# ESP32V1_based_led_button.net
KiCad netlist of a schematic drawn in EAGLE
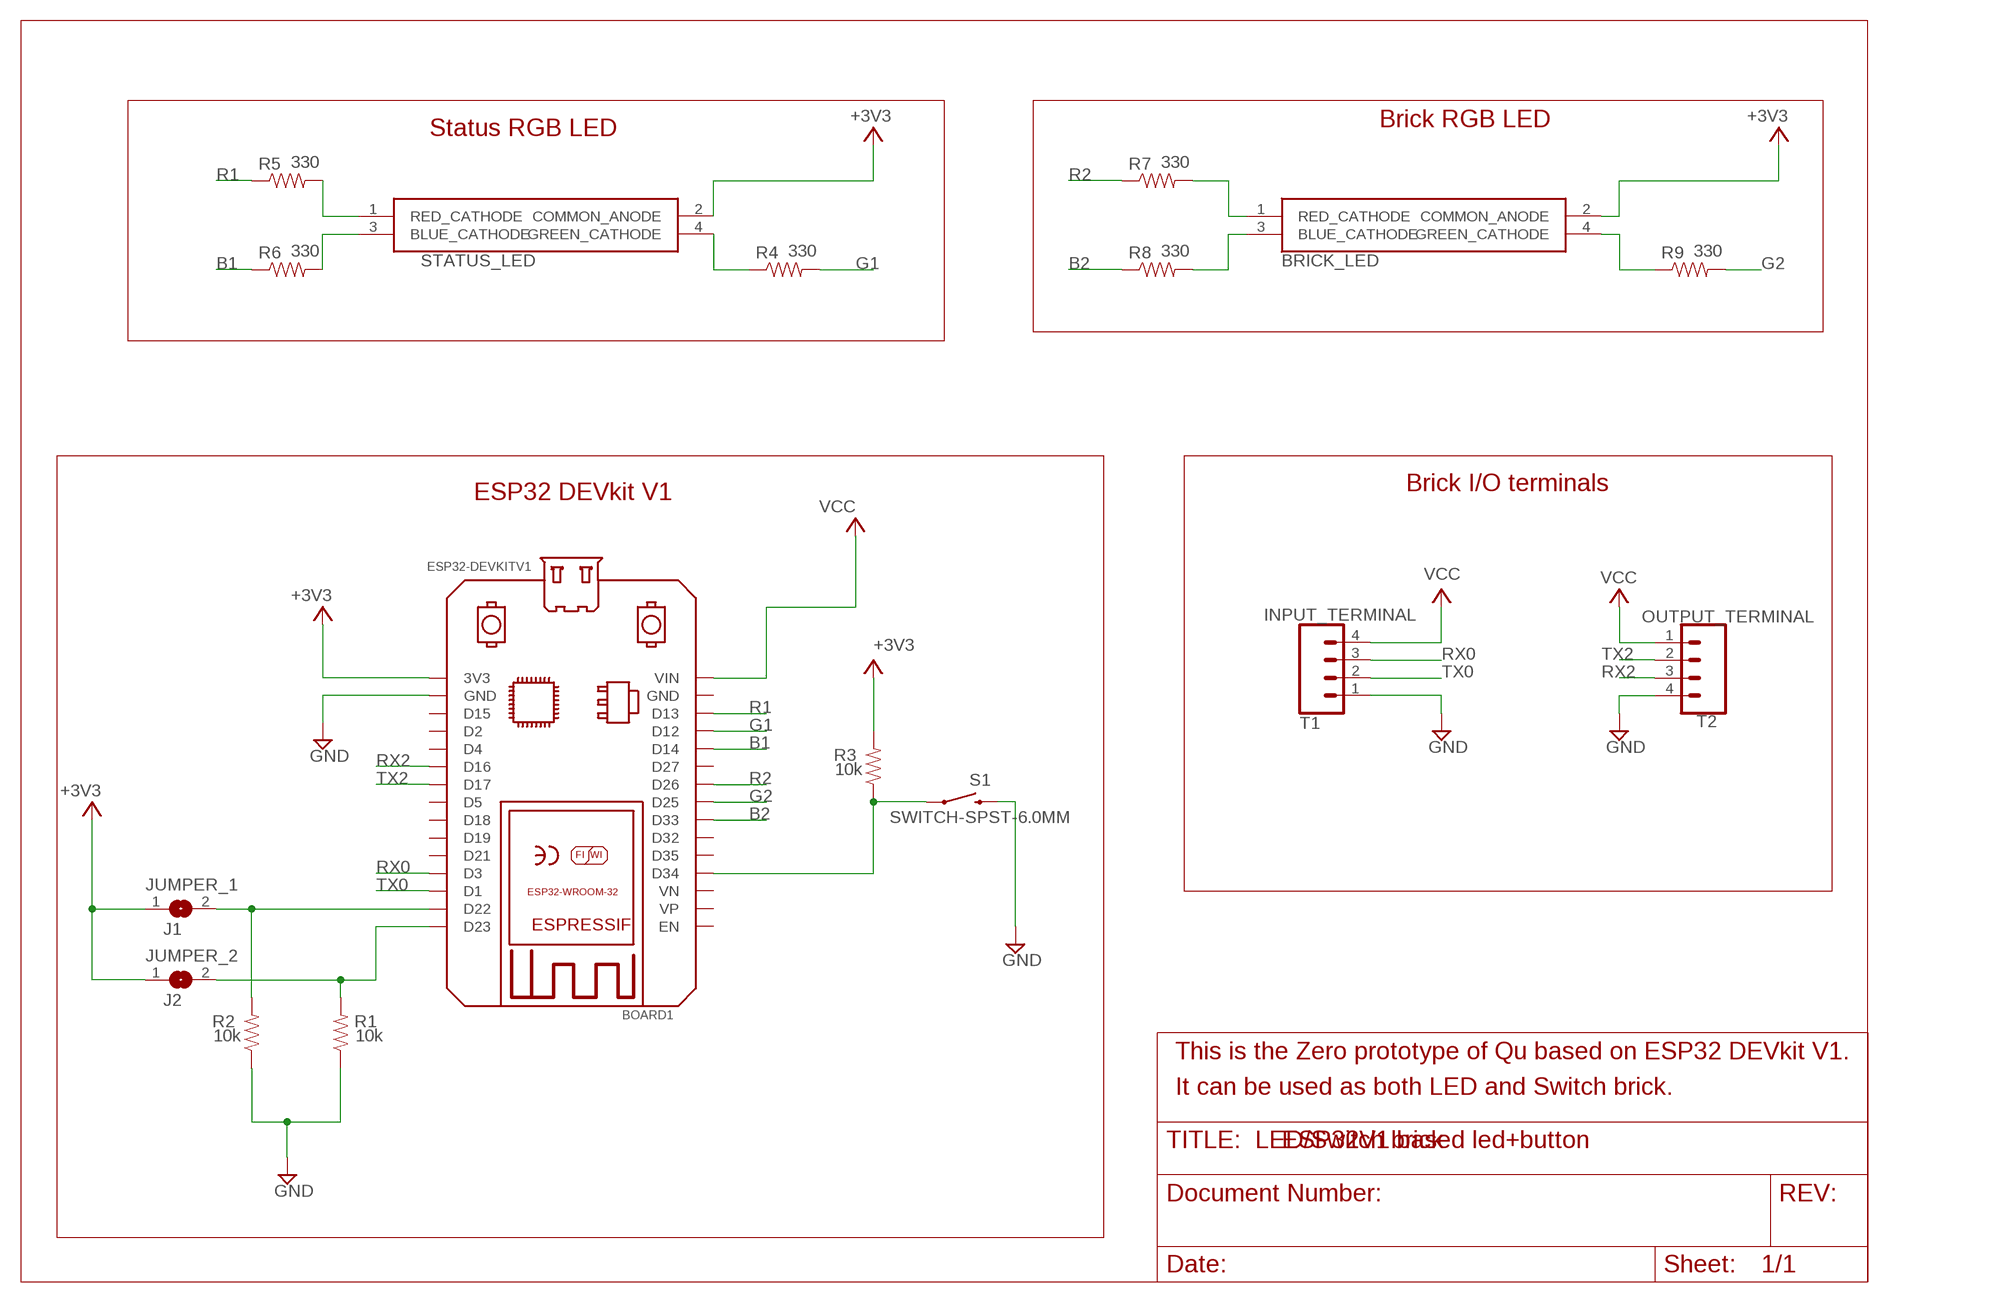
[diagram p0: schematic, sheet 1]

(export (version "E")
  (design (tool "Eeschema 10.0.6"))
  (components
    (comp (ref "BOARD1")
      (value "ESP32DEVKITV1")
      (footprint "eagle-import:ESP32-DEVKITV1")
      (libsource (lib "eagle-import") (part "ESP32DEVKITV1"))
    )
    (comp (ref "BRICK_LED")
      (value "WP154A4SEJ3VBDZGW_CA")
      (footprint "eagle-import:L-154A4SUREQBFZGEC")
      (fields
        (field (name "MANUFACTURER_PART_NUMBER") "WP154A4SEJ3VBDZGW/CA")
        (field (name "MOUSER_PART_NUMBER") "604-WP154A43VBDZGWCA")
      )
      (libsource (lib "eagle-import") (part "WP154A4SEJ3VBDZGW_CA"))
    )
    (comp (ref "INPUT_TERMINAL")
      (value "T1")
      (footprint "eagle-import:1X04")
      (libsource (lib "eagle-import") (part "CONN_04"))
    )
    (comp (ref "JUMPER_1")
      (value "J1")
      (footprint "eagle-import:SJW")
      (libsource (lib "eagle-import") (part "SJW"))
    )
    (comp (ref "JUMPER_2")
      (value "J2")
      (footprint "eagle-import:SJW")
      (libsource (lib "eagle-import") (part "SJW"))
    )
    (comp (ref "OUTPUT_TERMINAL")
      (value "T2")
      (footprint "eagle-import:1X04")
      (libsource (lib "eagle-import") (part "CONN_04"))
    )
    (comp (ref "R1")
      (value "10k")
      (footprint "eagle-import:AXIAL-0.3")
      (libsource (lib "eagle-import") (part "10KOHM-HORIZ-1/4W-1%"))
    )
    (comp (ref "R2")
      (value "10k")
      (footprint "eagle-import:AXIAL-0.3")
      (libsource (lib "eagle-import") (part "10KOHM-HORIZ-1/4W-1%"))
    )
    (comp (ref "R3")
      (value "10k")
      (footprint "eagle-import:AXIAL-0.3")
      (libsource (lib "eagle-import") (part "10KOHM-HORIZ-1/4W-1%"))
    )
    (comp (ref "R4")
      (value "330")
      (footprint "eagle-import:AXIAL-0.3")
      (libsource (lib "eagle-import") (part "330OHM-HORIZ-1/10W-5%"))
    )
    (comp (ref "R5")
      (value "330")
      (footprint "eagle-import:AXIAL-0.3")
      (libsource (lib "eagle-import") (part "330OHM-HORIZ-1/10W-5%"))
    )
    (comp (ref "R6")
      (value "330")
      (footprint "eagle-import:AXIAL-0.3")
      (libsource (lib "eagle-import") (part "330OHM-HORIZ-1/10W-5%"))
    )
    (comp (ref "R7")
      (value "330")
      (footprint "eagle-import:AXIAL-0.3")
      (libsource (lib "eagle-import") (part "330OHM-HORIZ-1/10W-5%"))
    )
    (comp (ref "R8")
      (value "330")
      (footprint "eagle-import:AXIAL-0.3")
      (libsource (lib "eagle-import") (part "330OHM-HORIZ-1/10W-5%"))
    )
    (comp (ref "R9")
      (value "330")
      (footprint "eagle-import:AXIAL-0.3")
      (libsource (lib "eagle-import") (part "330OHM-HORIZ-1/10W-5%"))
    )
    (comp (ref "S1")
      (value "SWITCH-SPST-6.0MM")
      (footprint "eagle-import:TACTILE_SWITCH_PTH_6.0MM_KIT")
      (libsource (lib "eagle-import") (part "MOMENTARY-SWITCH-SPST-PTH-6.0MM-KIT"))
    )
    (comp (ref "STATUS_LED")
      (value "WP154A4SEJ3VBDZGW_CA")
      (footprint "eagle-import:L-154A4SUREQBFZGEC")
      (fields
        (field (name "MANUFACTURER_PART_NUMBER") "WP154A4SEJ3VBDZGW/CA")
        (field (name "MOUSER_PART_NUMBER") "604-WP154A43VBDZGWCA")
      )
      (libsource (lib "eagle-import") (part "WP154A4SEJ3VBDZGW_CA"))
    )
  )
  (nets
    (net (code "1") (name "+3V3") (class "Default")
      (node (ref "BOARD1") (pin "3V3") (pinfunction "3V3_3V3") (pintype "bidirectional"))
      (node (ref "BRICK_LED") (pin "2") (pinfunction "COMMON_ANODE_2") (pintype "bidirectional"))
      (node (ref "JUMPER_1") (pin "1") (pinfunction "1_1") (pintype "passive"))
      (node (ref "JUMPER_2") (pin "1") (pinfunction "1_1") (pintype "passive"))
      (node (ref "R3") (pin "P$2") (pinfunction "2_P$2") (pintype "passive"))
      (node (ref "STATUS_LED") (pin "2") (pinfunction "COMMON_ANODE_2") (pintype "bidirectional"))
    )
    (net (code "2") (name "/B1") (class "Default")
      (node (ref "BOARD1") (pin "D14") (pinfunction "D14_D14") (pintype "bidirectional"))
      (node (ref "R6") (pin "P$1") (pinfunction "1_P$1") (pintype "passive"))
    )
    (net (code "3") (name "/B2") (class "Default")
      (node (ref "BOARD1") (pin "D33") (pinfunction "D33_D33") (pintype "bidirectional"))
      (node (ref "R8") (pin "P$1") (pinfunction "1_P$1") (pintype "passive"))
    )
    (net (code "4") (name "/G1") (class "Default")
      (node (ref "BOARD1") (pin "D12") (pinfunction "D12_D12") (pintype "bidirectional"))
      (node (ref "R4") (pin "P$2") (pinfunction "2_P$2") (pintype "passive"))
    )
    (net (code "5") (name "/G2") (class "Default")
      (node (ref "BOARD1") (pin "D25") (pinfunction "D25_D25") (pintype "bidirectional"))
      (node (ref "R9") (pin "P$2") (pinfunction "2_P$2") (pintype "passive"))
    )
    (net (code "6") (name "/R1") (class "Default")
      (node (ref "BOARD1") (pin "D13") (pinfunction "D13_D13") (pintype "bidirectional"))
      (node (ref "R5") (pin "P$1") (pinfunction "1_P$1") (pintype "passive"))
    )
    (net (code "7") (name "/R2") (class "Default")
      (node (ref "BOARD1") (pin "D26") (pinfunction "D26_D26") (pintype "bidirectional"))
      (node (ref "R7") (pin "P$1") (pinfunction "1_P$1") (pintype "passive"))
    )
    (net (code "8") (name "/RX0") (class "Default")
      (node (ref "BOARD1") (pin "D3") (pinfunction "D3_D3") (pintype "bidirectional"))
      (node (ref "INPUT_TERMINAL") (pin "3") (pinfunction "3_3") (pintype "passive"))
    )
    (net (code "9") (name "/RX2") (class "Default")
      (node (ref "BOARD1") (pin "D16") (pinfunction "D16_D16") (pintype "bidirectional"))
      (node (ref "OUTPUT_TERMINAL") (pin "3") (pinfunction "3_3") (pintype "passive"))
    )
    (net (code "10") (name "/TX0") (class "Default")
      (node (ref "BOARD1") (pin "D1") (pinfunction "D1_D1") (pintype "bidirectional"))
      (node (ref "INPUT_TERMINAL") (pin "2") (pinfunction "2_2") (pintype "passive"))
    )
    (net (code "11") (name "/TX2") (class "Default")
      (node (ref "BOARD1") (pin "D17") (pinfunction "D17_D17") (pintype "bidirectional"))
      (node (ref "OUTPUT_TERMINAL") (pin "2") (pinfunction "2_2") (pintype "passive"))
    )
    (net (code "12") (name "GND") (class "Default")
      (node (ref "BOARD1") (pin "GND@1") (pinfunction "GND_GND@1") (pintype "bidirectional"))
      (node (ref "INPUT_TERMINAL") (pin "1") (pinfunction "1_1") (pintype "passive"))
      (node (ref "OUTPUT_TERMINAL") (pin "4") (pinfunction "4_4") (pintype "passive"))
      (node (ref "R1") (pin "P$1") (pinfunction "1_P$1") (pintype "passive"))
      (node (ref "R2") (pin "P$1") (pinfunction "1_P$1") (pintype "passive"))
      (node (ref "S1") (pin "3") (pinfunction "2_3") (pintype "passive"))
    )
    (net (code "13") (name "Net-(BRICK_LED-BLUE_CATHODE)") (class "Default")
      (node (ref "BRICK_LED") (pin "3") (pinfunction "BLUE_CATHODE_3") (pintype "bidirectional"))
      (node (ref "R8") (pin "P$2") (pinfunction "2_P$2") (pintype "passive"))
    )
    (net (code "14") (name "Net-(BRICK_LED-GREEN_CATHODE)") (class "Default")
      (node (ref "BRICK_LED") (pin "4") (pinfunction "GREEN_CATHODE_4") (pintype "bidirectional"))
      (node (ref "R9") (pin "P$1") (pinfunction "1_P$1") (pintype "passive"))
    )
    (net (code "15") (name "Net-(BRICK_LED-RED_CATHODE)") (class "Default")
      (node (ref "BRICK_LED") (pin "1") (pinfunction "RED_CATHODE_1") (pintype "bidirectional"))
      (node (ref "R7") (pin "P$2") (pinfunction "2_P$2") (pintype "passive"))
    )
    (net (code "16") (name "Net-(R1-2)") (class "Default")
      (node (ref "BOARD1") (pin "D23") (pinfunction "D23_D23") (pintype "bidirectional"))
      (node (ref "JUMPER_2") (pin "2") (pinfunction "2_2") (pintype "passive"))
      (node (ref "R1") (pin "P$2") (pinfunction "2_P$2") (pintype "passive"))
    )
    (net (code "17") (name "Net-(R2-2)") (class "Default")
      (node (ref "BOARD1") (pin "D22") (pinfunction "D22_D22") (pintype "bidirectional"))
      (node (ref "JUMPER_1") (pin "2") (pinfunction "2_2") (pintype "passive"))
      (node (ref "R2") (pin "P$2") (pinfunction "2_P$2") (pintype "passive"))
    )
    (net (code "18") (name "Net-(R3-1)") (class "Default")
      (node (ref "BOARD1") (pin "D34") (pinfunction "D34_D34") (pintype "bidirectional"))
      (node (ref "R3") (pin "P$1") (pinfunction "1_P$1") (pintype "passive"))
      (node (ref "S1") (pin "1") (pinfunction "1_1") (pintype "passive"))
    )
    (net (code "19") (name "Net-(R4-1)") (class "Default")
      (node (ref "R4") (pin "P$1") (pinfunction "1_P$1") (pintype "passive"))
      (node (ref "STATUS_LED") (pin "4") (pinfunction "GREEN_CATHODE_4") (pintype "bidirectional"))
    )
    (net (code "20") (name "Net-(R5-2)") (class "Default")
      (node (ref "R5") (pin "P$2") (pinfunction "2_P$2") (pintype "passive"))
      (node (ref "STATUS_LED") (pin "1") (pinfunction "RED_CATHODE_1") (pintype "bidirectional"))
    )
    (net (code "21") (name "Net-(R6-2)") (class "Default")
      (node (ref "R6") (pin "P$2") (pinfunction "2_P$2") (pintype "passive"))
      (node (ref "STATUS_LED") (pin "3") (pinfunction "BLUE_CATHODE_3") (pintype "bidirectional"))
    )
    (net (code "22") (name "VCC") (class "Default")
      (node (ref "BOARD1") (pin "VIN") (pinfunction "VIN_VIN") (pintype "bidirectional"))
      (node (ref "INPUT_TERMINAL") (pin "4") (pinfunction "4_4") (pintype "passive"))
      (node (ref "OUTPUT_TERMINAL") (pin "1") (pinfunction "1_1") (pintype "passive"))
    )
    (net (code "23") (name "unconnected-(BOARD1-PadD2)") (class "Default")
      (node (ref "BOARD1") (pin "D2") (pinfunction "D2_D2") (pintype "bidirectional"))
    )
    (net (code "24") (name "unconnected-(BOARD1-PadD4)") (class "Default")
      (node (ref "BOARD1") (pin "D4") (pinfunction "D4_D4") (pintype "bidirectional"))
    )
    (net (code "25") (name "unconnected-(BOARD1-PadD5)") (class "Default")
      (node (ref "BOARD1") (pin "D5") (pinfunction "D5_D5") (pintype "bidirectional"))
    )
    (net (code "26") (name "unconnected-(BOARD1-PadD15)") (class "Default")
      (node (ref "BOARD1") (pin "D15") (pinfunction "D15_D15") (pintype "bidirectional"))
    )
    (net (code "27") (name "unconnected-(BOARD1-PadD18)") (class "Default")
      (node (ref "BOARD1") (pin "D18") (pinfunction "D18_D18") (pintype "bidirectional"))
    )
    (net (code "28") (name "unconnected-(BOARD1-PadD19)") (class "Default")
      (node (ref "BOARD1") (pin "D19") (pinfunction "D19_D19") (pintype "bidirectional"))
    )
    (net (code "29") (name "unconnected-(BOARD1-PadD21)") (class "Default")
      (node (ref "BOARD1") (pin "D21") (pinfunction "D21_D21") (pintype "bidirectional"))
    )
    (net (code "30") (name "unconnected-(BOARD1-PadD27)") (class "Default")
      (node (ref "BOARD1") (pin "D27") (pinfunction "D27_D27") (pintype "bidirectional"))
    )
    (net (code "31") (name "unconnected-(BOARD1-PadD32)") (class "Default")
      (node (ref "BOARD1") (pin "D32") (pinfunction "D32_D32") (pintype "bidirectional"))
    )
    (net (code "32") (name "unconnected-(BOARD1-PadD35)") (class "Default")
      (node (ref "BOARD1") (pin "D35") (pinfunction "D35_D35") (pintype "bidirectional"))
    )
    (net (code "33") (name "unconnected-(BOARD1-PadEN)") (class "Default")
      (node (ref "BOARD1") (pin "EN") (pinfunction "EN_EN") (pintype "bidirectional"))
    )
    (net (code "34") (name "unconnected-(BOARD1-PadGND)") (class "Default")
      (node (ref "BOARD1") (pin "GND") (pinfunction "GND_GND") (pintype "bidirectional"))
    )
    (net (code "35") (name "unconnected-(BOARD1-PadVN)") (class "Default")
      (node (ref "BOARD1") (pin "VN") (pinfunction "VN_VN") (pintype "bidirectional"))
    )
    (net (code "36") (name "unconnected-(BOARD1-PadVP)") (class "Default")
      (node (ref "BOARD1") (pin "VP") (pinfunction "VP_VP") (pintype "bidirectional"))
    )
  )
)
